# 02_ESP12_CORE.net
KiCad netlist of a schematic drawn in Altium Designer
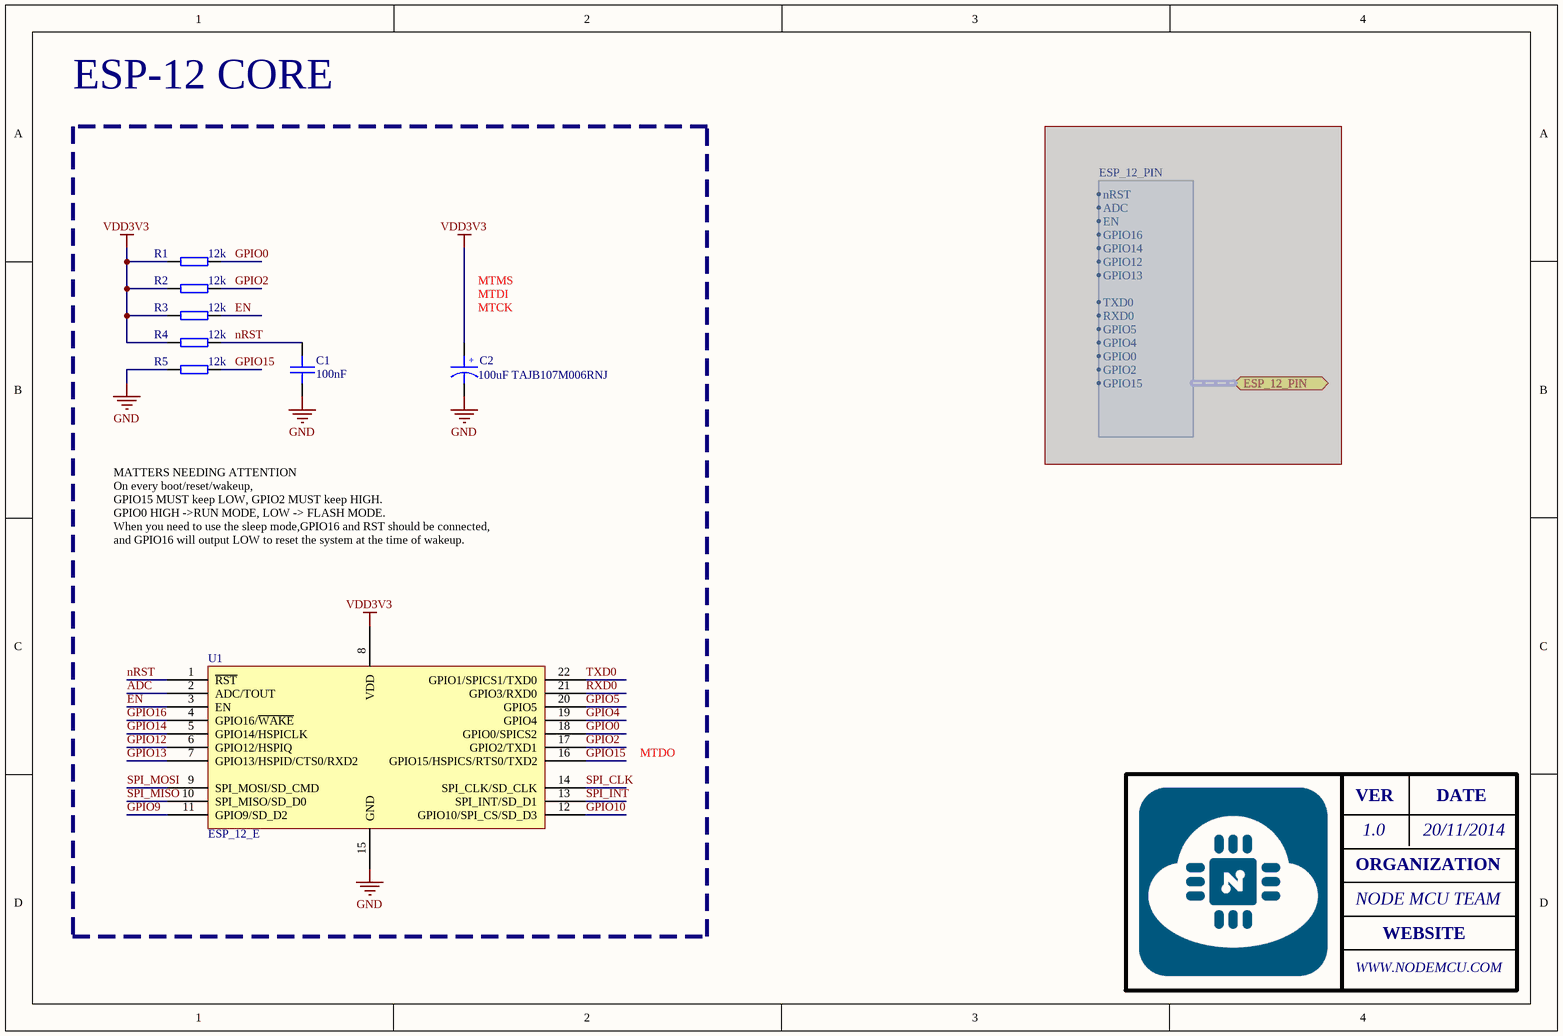
[diagram p0: 02_ESP12_CORE.SchDoc]

(export (version "E")
  (design (tool "Eeschema 10.0.6"))
  (components
    (comp (ref "C1")
      (value "100nF")
      (footprint "SMT_C_0402")
      (description "Surface mount capacitor 0402")
      (libsource (lib "Vowstar_Basic_Device") (part "SMT_C_0402"))
    )
    (comp (ref "C2")
      (value "100uF TAJB107M006RNJ")
      (footprint "SMT_C_Tantalum_B")
      (description "Capacitor, SM Tantalum; Body 3.5 x 2.8 mm (LxW typ)")
      (libsource (lib "Vowstar_Basic_Device") (part "SMT_C_Tantalum_B"))
    )
    (comp (ref "R1")
      (value "12k")
      (footprint "SMT_R_0603")
      (description "Surface mount resistor 0402")
      (libsource (lib "Vowstar_Basic_Device") (part "SMT_R_0402"))
    )
    (comp (ref "R2")
      (value "12k")
      (footprint "SMT_R_0603")
      (description "Surface mount resistor 0402")
      (libsource (lib "Vowstar_Basic_Device") (part "SMT_R_0402"))
    )
    (comp (ref "R3")
      (value "12k")
      (footprint "SMT_R_0603")
      (description "Surface mount resistor 0402")
      (libsource (lib "Vowstar_Basic_Device") (part "SMT_R_0402"))
    )
    (comp (ref "R4")
      (value "12k")
      (footprint "SMT_R_0603")
      (description "Surface mount resistor 0402")
      (libsource (lib "Vowstar_Basic_Device") (part "SMT_R_0402"))
    )
    (comp (ref "R5")
      (value "12k")
      (footprint "SMT_R_0603")
      (description "Surface mount resistor 0402")
      (libsource (lib "Vowstar_Basic_Device") (part "SMT_R_0402"))
    )
    (comp (ref "U1")
      (value "ESP_12_E")
      (footprint "ESP_12_E_L")
      (description "ESP-12 Wi-Fi Module by AI-Thinker")
      (libsource (lib "Vowstar_Module") (part "ESP_12_E"))
    )
  )
  (nets
    (net (code "2") (name "/ADC") (class "Default")
      (node (ref "U1") (pin "2") (pinfunction "ADC/TOUT_2") (pintype "passive"))
    )
    (net (code "3") (name "/EN") (class "Default")
      (node (ref "R3") (pin "2") (pinfunction "2_2") (pintype "passive"))
      (node (ref "U1") (pin "3") (pinfunction "EN_3") (pintype "passive"))
    )
    (net (code "4") (name "/GPIO0") (class "Default")
      (node (ref "R1") (pin "2") (pinfunction "2_2") (pintype "passive"))
      (node (ref "U1") (pin "18") (pinfunction "GPIO0/SPICS2_18") (pintype "passive"))
    )
    (net (code "5") (name "/GPIO2") (class "Default")
      (node (ref "R2") (pin "2") (pinfunction "2_2") (pintype "passive"))
      (node (ref "U1") (pin "17") (pinfunction "GPIO2/TXD1_17") (pintype "passive"))
    )
    (net (code "6") (name "/GPIO4") (class "Default")
      (node (ref "U1") (pin "19") (pinfunction "GPIO4_19") (pintype "passive"))
    )
    (net (code "7") (name "/GPIO5") (class "Default")
      (node (ref "U1") (pin "20") (pinfunction "GPIO5_20") (pintype "passive"))
    )
    (net (code "8") (name "/GPIO9") (class "Default")
      (node (ref "U1") (pin "11") (pinfunction "GPIO9/SD_D2_11") (pintype "passive"))
    )
    (net (code "9") (name "/GPIO10") (class "Default")
      (node (ref "U1") (pin "12") (pinfunction "GPIO10/SPI_CS/SD_D3_12") (pintype "passive"))
    )
    (net (code "10") (name "/GPIO12") (class "Default")
      (node (ref "U1") (pin "6") (pinfunction "GPIO12/HSPIQ_6") (pintype "passive"))
    )
    (net (code "11") (name "/GPIO13") (class "Default")
      (node (ref "U1") (pin "7") (pinfunction "GPIO13/HSPID/CTS0/RXD2_7") (pintype "passive"))
    )
    (net (code "12") (name "/GPIO14") (class "Default")
      (node (ref "U1") (pin "5") (pinfunction "GPIO14/HSPICLK_5") (pintype "passive"))
    )
    (net (code "13") (name "/GPIO15") (class "Default")
      (node (ref "R5") (pin "2") (pinfunction "2_2") (pintype "passive"))
      (node (ref "U1") (pin "16") (pinfunction "GPIO15/HSPICS/RTS0/TXD2_16") (pintype "passive"))
    )
    (net (code "14") (name "/GPIO16") (class "Default")
      (node (ref "U1") (pin "4") (pinfunction "GPIO16/~{WAKE}_4") (pintype "passive"))
    )
    (net (code "15") (name "/RXD0") (class "Default")
      (node (ref "U1") (pin "21") (pinfunction "GPIO3/RXD0_21") (pintype "passive"))
    )
    (net (code "16") (name "/SPI_CLK") (class "Default")
      (node (ref "U1") (pin "14") (pinfunction "SPI_CLK/SD_CLK_14") (pintype "passive"))
    )
    (net (code "17") (name "/SPI_INT") (class "Default")
      (node (ref "U1") (pin "13") (pinfunction "SPI_INT/SD_D1_13") (pintype "passive"))
    )
    (net (code "18") (name "/SPI_MISO") (class "Default")
      (node (ref "U1") (pin "10") (pinfunction "SPI_MISO/SD_D0_10") (pintype "passive"))
    )
    (net (code "19") (name "/SPI_MOSI") (class "Default")
      (node (ref "U1") (pin "9") (pinfunction "SPI_MOSI/SD_CMD_9") (pintype "passive"))
    )
    (net (code "20") (name "/TXD0") (class "Default")
      (node (ref "U1") (pin "22") (pinfunction "GPIO1/SPICS1/TXD0_22") (pintype "passive"))
    )
    (net (code "21") (name "/nRST") (class "Default")
      (node (ref "C1") (pin "1") (pinfunction "1_1") (pintype "passive"))
      (node (ref "R4") (pin "2") (pinfunction "2_2") (pintype "passive"))
      (node (ref "U1") (pin "1") (pinfunction "~{RST}_1") (pintype "passive"))
    )
    (net (code "23") (name "GND") (class "Default")
      (node (ref "C1") (pin "2") (pinfunction "2_2") (pintype "passive"))
      (node (ref "C2") (pin "2") (pinfunction "2_2") (pintype "passive"))
      (node (ref "R5") (pin "1") (pinfunction "1_1") (pintype "passive"))
      (node (ref "U1") (pin "15") (pinfunction "GND_15") (pintype "passive"))
    )
    (net (code "24") (name "VDD3V3") (class "Default")
      (node (ref "C2") (pin "1") (pinfunction "1_1") (pintype "passive"))
      (node (ref "R1") (pin "1") (pinfunction "1_1") (pintype "passive"))
      (node (ref "R2") (pin "1") (pinfunction "1_1") (pintype "passive"))
      (node (ref "R3") (pin "1") (pinfunction "1_1") (pintype "passive"))
      (node (ref "R4") (pin "1") (pinfunction "1_1") (pintype "passive"))
      (node (ref "U1") (pin "8") (pinfunction "VDD_8") (pintype "passive"))
    )
  )
)
